# rasp_sheild_i2c.net
KiCad netlist of a schematic drawn in Altium Designer
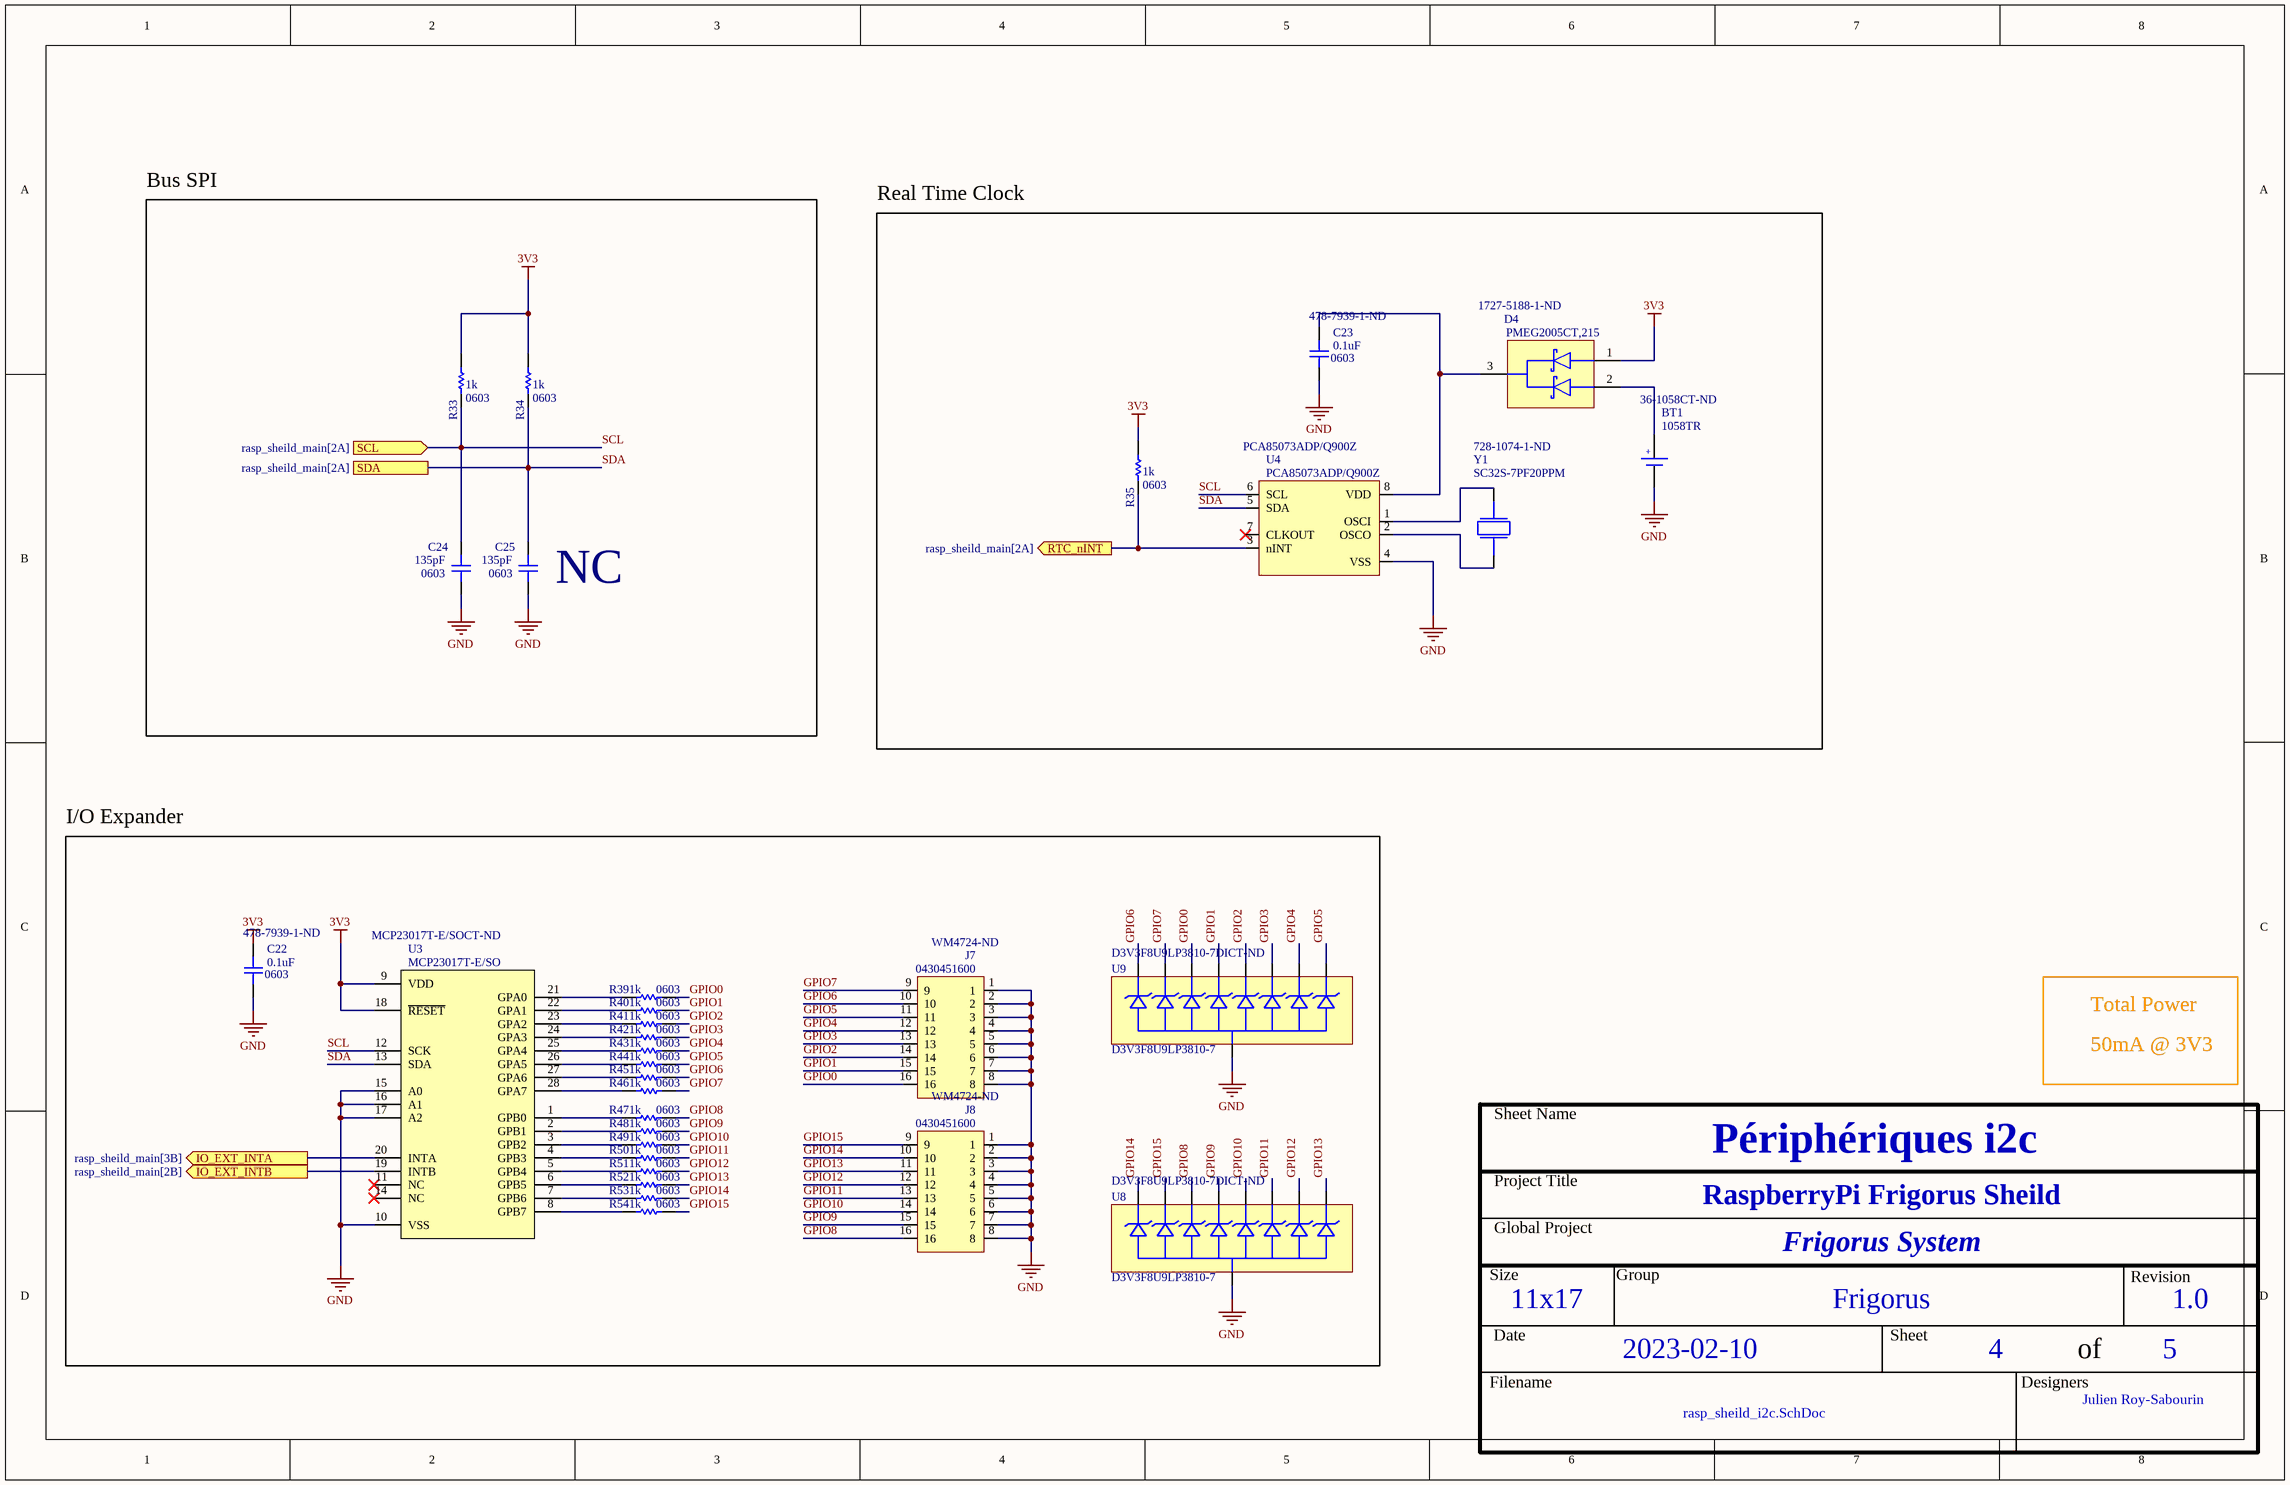
[diagram p0: rasp_sheild_i2c.SchDoc]

(export (version "E")
  (design (tool "Eeschema 10.0.6"))
  (components
    (comp (ref "BT1")
      (value "1058TR")
      (footprint "1058TR")
      (description "Battery Holder (Open) Coin, 20.0mm 1 Cell SMD (SMT) Tab")
      (fields (field (name "SUPPLIER PART NUMBER 1") "36-1058CT-ND"))
      (libsource (lib "royj1311") (part "1058TR"))
    )
    (comp (ref "C22")
      (value "0.1uF")
      (footprint "CAP_0603")
      (description "XXX - Description - Package")
      (fields
        (field (name "PACKAGE") "0603")
        (field (name "SUPPLIER PART NUMBER 1") "478-7939-1-ND")
        (field (name "Comment") "Part Number")
      )
      (libsource (lib "royj1311") (part "CAP_0603"))
    )
    (comp (ref "C23")
      (value "0.1uF")
      (footprint "CAP_0603")
      (description "XXX - Description - Package")
      (fields
        (field (name "PACKAGE") "0603")
        (field (name "SUPPLIER PART NUMBER 1") "478-7939-1-ND")
        (field (name "Comment") "Part Number")
      )
      (libsource (lib "royj1311") (part "CAP_0603"))
    )
    (comp (ref "C24")
      (value "135pF")
      (footprint "CAP_0603")
      (description "XXX - Description - Package")
      (fields (field (name "PACKAGE") "0603") (field (name "Comment") "Part Number"))
      (libsource (lib "royj1311") (part "CAP_0603"))
    )
    (comp (ref "C25")
      (value "135pF")
      (footprint "CAP_0603")
      (description "XXX - Description - Package")
      (fields (field (name "PACKAGE") "0603") (field (name "Comment") "Part Number"))
      (libsource (lib "royj1311") (part "CAP_0603"))
    )
    (comp (ref "D4")
      (value "PMEG2005CT,215")
      (footprint "SOT-23-3")
      (description "Diode Array 1 Pair Common Cathode 20 V 500mA Surface Mount TO-236-3, SC-59, SOT-23-3")
      (fields (field (name "SUPPLIER PART NUMBER 1") "1727-5188-1-ND"))
      (libsource (lib "royj1311") (part "PMEG2005CT,215"))
    )
    (comp (ref "J7")
      (value "0430451600")
      (footprint "0430451600")
      (description "Connector Header Through Hole, Right Angle 16 position 0.118\" (3.00mm)")
      (fields (field (name "SUPPLIER PART NUMBER 1") "WM4724-ND"))
      (libsource (lib "royj1311") (part "0430451600"))
    )
    (comp (ref "J8")
      (value "0430451600")
      (footprint "0430451600")
      (description "Connector Header Through Hole, Right Angle 16 position 0.118\" (3.00mm)")
      (fields (field (name "SUPPLIER PART NUMBER 1") "WM4724-ND"))
      (libsource (lib "royj1311") (part "0430451600"))
    )
    (comp (ref "R33")
      (value "1k")
      (footprint "RES_0603")
      (description "XXX - Description - Package")
      (fields (field (name "PACKAGE") "0603") (field (name "Comment") "Part Number"))
      (libsource (lib "royj1311") (part "RES_0603"))
    )
    (comp (ref "R34")
      (value "1k")
      (footprint "RES_0603")
      (description "XXX - Description - Package")
      (fields (field (name "PACKAGE") "0603") (field (name "Comment") "Part Number"))
      (libsource (lib "royj1311") (part "RES_0603"))
    )
    (comp (ref "R35")
      (value "1k")
      (footprint "RES_0603")
      (description "XXX - Description - Package")
      (fields (field (name "PACKAGE") "0603") (field (name "Comment") "Part Number"))
      (libsource (lib "royj1311") (part "RES_0603"))
    )
    (comp (ref "R39")
      (value "1k")
      (footprint "RES_0603")
      (description "XXX - Description - Package")
      (fields (field (name "PACKAGE") "0603") (field (name "Comment") "Part Number"))
      (libsource (lib "royj1311") (part "RES_0603"))
    )
    (comp (ref "R40")
      (value "1k")
      (footprint "RES_0603")
      (description "XXX - Description - Package")
      (fields (field (name "PACKAGE") "0603") (field (name "Comment") "Part Number"))
      (libsource (lib "royj1311") (part "RES_0603"))
    )
    (comp (ref "R41")
      (value "1k")
      (footprint "RES_0603")
      (description "XXX - Description - Package")
      (fields (field (name "PACKAGE") "0603") (field (name "Comment") "Part Number"))
      (libsource (lib "royj1311") (part "RES_0603"))
    )
    (comp (ref "R42")
      (value "1k")
      (footprint "RES_0603")
      (description "XXX - Description - Package")
      (fields (field (name "PACKAGE") "0603") (field (name "Comment") "Part Number"))
      (libsource (lib "royj1311") (part "RES_0603"))
    )
    (comp (ref "R43")
      (value "1k")
      (footprint "RES_0603")
      (description "XXX - Description - Package")
      (fields (field (name "PACKAGE") "0603") (field (name "Comment") "Part Number"))
      (libsource (lib "royj1311") (part "RES_0603"))
    )
    (comp (ref "R44")
      (value "1k")
      (footprint "RES_0603")
      (description "XXX - Description - Package")
      (fields (field (name "PACKAGE") "0603") (field (name "Comment") "Part Number"))
      (libsource (lib "royj1311") (part "RES_0603"))
    )
    (comp (ref "R45")
      (value "1k")
      (footprint "RES_0603")
      (description "XXX - Description - Package")
      (fields (field (name "PACKAGE") "0603") (field (name "Comment") "Part Number"))
      (libsource (lib "royj1311") (part "RES_0603"))
    )
    (comp (ref "R46")
      (value "1k")
      (footprint "RES_0603")
      (description "XXX - Description - Package")
      (fields (field (name "PACKAGE") "0603") (field (name "Comment") "Part Number"))
      (libsource (lib "royj1311") (part "RES_0603"))
    )
    (comp (ref "R47")
      (value "1k")
      (footprint "RES_0603")
      (description "XXX - Description - Package")
      (fields (field (name "PACKAGE") "0603") (field (name "Comment") "Part Number"))
      (libsource (lib "royj1311") (part "RES_0603"))
    )
    (comp (ref "R48")
      (value "1k")
      (footprint "RES_0603")
      (description "XXX - Description - Package")
      (fields (field (name "PACKAGE") "0603") (field (name "Comment") "Part Number"))
      (libsource (lib "royj1311") (part "RES_0603"))
    )
    (comp (ref "R49")
      (value "1k")
      (footprint "RES_0603")
      (description "XXX - Description - Package")
      (fields (field (name "PACKAGE") "0603") (field (name "Comment") "Part Number"))
      (libsource (lib "royj1311") (part "RES_0603"))
    )
    (comp (ref "R50")
      (value "1k")
      (footprint "RES_0603")
      (description "XXX - Description - Package")
      (fields (field (name "PACKAGE") "0603") (field (name "Comment") "Part Number"))
      (libsource (lib "royj1311") (part "RES_0603"))
    )
    (comp (ref "R51")
      (value "1k")
      (footprint "RES_0603")
      (description "XXX - Description - Package")
      (fields (field (name "PACKAGE") "0603") (field (name "Comment") "Part Number"))
      (libsource (lib "royj1311") (part "RES_0603"))
    )
    (comp (ref "R52")
      (value "1k")
      (footprint "RES_0603")
      (description "XXX - Description - Package")
      (fields (field (name "PACKAGE") "0603") (field (name "Comment") "Part Number"))
      (libsource (lib "royj1311") (part "RES_0603"))
    )
    (comp (ref "R53")
      (value "1k")
      (footprint "RES_0603")
      (description "XXX - Description - Package")
      (fields (field (name "PACKAGE") "0603") (field (name "Comment") "Part Number"))
      (libsource (lib "royj1311") (part "RES_0603"))
    )
    (comp (ref "R54")
      (value "1k")
      (footprint "RES_0603")
      (description "XXX - Description - Package")
      (fields (field (name "PACKAGE") "0603") (field (name "Comment") "Part Number"))
      (libsource (lib "royj1311") (part "RES_0603"))
    )
    (comp (ref "U3")
      (value "MCP23017T-E/SO")
      (footprint "28-SOIC")
      (description "I/O Expander 16 I²C 1.7 MHz 28-SOIC")
      (fields (field (name "SUPPLIER PART NUMBER 1") "MCP23017T-E/SOCT-ND"))
      (libsource (lib "royj1311") (part "MCP23017T-E/SO"))
    )
    (comp (ref "U4")
      (value "PCA85073ADP/Q900Z")
      (footprint "8-MSOP")
      (description "Real Time Clock (RTC) IC Clock/Calendar I²C 8-TSSOP, 8-MSOP (0.118\", 3.00mm Width)")
      (fields (field (name "SUPPLIER PART NUMBER 1") "PCA85073ADP/Q900Z"))
      (libsource (lib "royj1311") (part "PCA85073ADP/Q900Z"))
    )
    (comp (ref "U8")
      (value "D3V3F8U9LP3810-7")
      (footprint "D3V3F8U9LP3810-7")
      (description "5V (Typ) Clamp 5A (8/20µs) Ipp Tvs Diode Surface Mount U-DFN3810-9 (Type B)")
      (fields (field (name "SUPPLIER PART NUMBER 1") "D3V3F8U9LP3810-7DICT-ND"))
      (libsource (lib "royj1311") (part "D3V3F8U9LP3810-7"))
    )
    (comp (ref "U9")
      (value "D3V3F8U9LP3810-7")
      (footprint "D3V3F8U9LP3810-7")
      (description "5V (Typ) Clamp 5A (8/20µs) Ipp Tvs Diode Surface Mount U-DFN3810-9 (Type B)")
      (fields (field (name "SUPPLIER PART NUMBER 1") "D3V3F8U9LP3810-7DICT-ND"))
      (libsource (lib "royj1311") (part "D3V3F8U9LP3810-7"))
    )
    (comp (ref "Y1")
      (value "SC32S-7PF20PPM")
      (footprint "SC32S-7PF20PPM")
      (description "32.768 kHz ±20ppm Crystal 7pF 70 kOhms 2-SMD, No Lead")
      (fields (field (name "SUPPLIER PART NUMBER 1") "728-1074-1-ND"))
      (libsource (lib "royj1311") (part "SC32S-7PF20PPM"))
    )
  )
  (nets
    (net (code "1") (name "/GPIO0") (class "Default")
      (node (ref "J7") (pin "16") (pinfunction "16_16") (pintype "passive"))
      (node (ref "R39") (pin "1") (pinfunction "1_1") (pintype "passive"))
      (node (ref "U9") (pin "4") (pinfunction "4_4") (pintype "passive"))
    )
    (net (code "2") (name "/GPIO1") (class "Default")
      (node (ref "J7") (pin "15") (pinfunction "15_15") (pintype "passive"))
      (node (ref "R40") (pin "1") (pinfunction "1_1") (pintype "passive"))
      (node (ref "U9") (pin "5") (pinfunction "5_5") (pintype "passive"))
    )
    (net (code "3") (name "/GPIO2") (class "Default")
      (node (ref "J7") (pin "14") (pinfunction "14_14") (pintype "passive"))
      (node (ref "R41") (pin "1") (pinfunction "1_1") (pintype "passive"))
      (node (ref "U9") (pin "6") (pinfunction "6_6") (pintype "passive"))
    )
    (net (code "4") (name "/GPIO3") (class "Default")
      (node (ref "J7") (pin "13") (pinfunction "13_13") (pintype "passive"))
      (node (ref "R42") (pin "1") (pinfunction "1_1") (pintype "passive"))
      (node (ref "U9") (pin "7") (pinfunction "7_7") (pintype "passive"))
    )
    (net (code "5") (name "/GPIO4") (class "Default")
      (node (ref "J7") (pin "12") (pinfunction "12_12") (pintype "passive"))
      (node (ref "R43") (pin "1") (pinfunction "1_1") (pintype "passive"))
      (node (ref "U9") (pin "8") (pinfunction "8_8") (pintype "passive"))
    )
    (net (code "6") (name "/GPIO5") (class "Default")
      (node (ref "J7") (pin "11") (pinfunction "11_11") (pintype "passive"))
      (node (ref "R44") (pin "1") (pinfunction "1_1") (pintype "passive"))
      (node (ref "U9") (pin "9") (pinfunction "9_9") (pintype "passive"))
    )
    (net (code "7") (name "/GPIO6") (class "Default")
      (node (ref "J7") (pin "10") (pinfunction "10_10") (pintype "passive"))
      (node (ref "R45") (pin "1") (pinfunction "1_1") (pintype "passive"))
      (node (ref "U9") (pin "1") (pinfunction "1_1") (pintype "passive"))
    )
    (net (code "8") (name "/GPIO7") (class "Default")
      (node (ref "J7") (pin "9") (pinfunction "9_9") (pintype "passive"))
      (node (ref "R46") (pin "1") (pinfunction "1_1") (pintype "passive"))
      (node (ref "U9") (pin "2") (pinfunction "2_2") (pintype "passive"))
    )
    (net (code "9") (name "/GPIO8") (class "Default")
      (node (ref "J8") (pin "16") (pinfunction "16_16") (pintype "passive"))
      (node (ref "R47") (pin "1") (pinfunction "1_1") (pintype "passive"))
      (node (ref "U8") (pin "4") (pinfunction "4_4") (pintype "passive"))
    )
    (net (code "10") (name "/GPIO9") (class "Default")
      (node (ref "J8") (pin "15") (pinfunction "15_15") (pintype "passive"))
      (node (ref "R48") (pin "1") (pinfunction "1_1") (pintype "passive"))
      (node (ref "U8") (pin "5") (pinfunction "5_5") (pintype "passive"))
    )
    (net (code "11") (name "/GPIO10") (class "Default")
      (node (ref "J8") (pin "14") (pinfunction "14_14") (pintype "passive"))
      (node (ref "R49") (pin "1") (pinfunction "1_1") (pintype "passive"))
      (node (ref "U8") (pin "6") (pinfunction "6_6") (pintype "passive"))
    )
    (net (code "12") (name "/GPIO11") (class "Default")
      (node (ref "J8") (pin "13") (pinfunction "13_13") (pintype "passive"))
      (node (ref "R50") (pin "1") (pinfunction "1_1") (pintype "passive"))
      (node (ref "U8") (pin "7") (pinfunction "7_7") (pintype "passive"))
    )
    (net (code "13") (name "/GPIO12") (class "Default")
      (node (ref "J8") (pin "12") (pinfunction "12_12") (pintype "passive"))
      (node (ref "R51") (pin "1") (pinfunction "1_1") (pintype "passive"))
      (node (ref "U8") (pin "8") (pinfunction "8_8") (pintype "passive"))
    )
    (net (code "14") (name "/GPIO13") (class "Default")
      (node (ref "J8") (pin "11") (pinfunction "11_11") (pintype "passive"))
      (node (ref "R52") (pin "1") (pinfunction "1_1") (pintype "passive"))
      (node (ref "U8") (pin "9") (pinfunction "9_9") (pintype "passive"))
    )
    (net (code "15") (name "/GPIO14") (class "Default")
      (node (ref "J8") (pin "10") (pinfunction "10_10") (pintype "passive"))
      (node (ref "R53") (pin "1") (pinfunction "1_1") (pintype "passive"))
      (node (ref "U8") (pin "1") (pinfunction "1_1") (pintype "passive"))
    )
    (net (code "16") (name "/GPIO15") (class "Default")
      (node (ref "J8") (pin "9") (pinfunction "9_9") (pintype "passive"))
      (node (ref "R54") (pin "1") (pinfunction "1_1") (pintype "passive"))
      (node (ref "U8") (pin "2") (pinfunction "2_2") (pintype "passive"))
    )
    (net (code "17") (name "/IO_EXT_INTA") (class "Default")
      (node (ref "U3") (pin "20") (pinfunction "INTA_20") (pintype "passive"))
    )
    (net (code "18") (name "/IO_EXT_INTB") (class "Default")
      (node (ref "U3") (pin "19") (pinfunction "INTB_19") (pintype "passive"))
    )
    (net (code "19") (name "/RTC_nINT") (class "Default")
      (node (ref "R35") (pin "2") (pinfunction "2_2") (pintype "passive"))
      (node (ref "U4") (pin "3") (pinfunction "nINT_3") (pintype "passive"))
    )
    (net (code "20") (name "/SCL") (class "Default")
      (node (ref "C24") (pin "2") (pinfunction "2_2") (pintype "passive"))
      (node (ref "R33") (pin "2") (pinfunction "2_2") (pintype "passive"))
      (node (ref "U3") (pin "12") (pinfunction "SCK_12") (pintype "passive"))
      (node (ref "U4") (pin "6") (pinfunction "SCL_6") (pintype "passive"))
    )
    (net (code "21") (name "/SDA") (class "Default")
      (node (ref "C25") (pin "2") (pinfunction "2_2") (pintype "passive"))
      (node (ref "R34") (pin "2") (pinfunction "2_2") (pintype "passive"))
      (node (ref "U3") (pin "13") (pinfunction "SDA_13") (pintype "passive"))
      (node (ref "U4") (pin "5") (pinfunction "SDA_5") (pintype "passive"))
    )
    (net (code "22") (name "3V3") (class "Default")
      (node (ref "C22") (pin "2") (pinfunction "2_2") (pintype "passive"))
      (node (ref "D4") (pin "1") (pinfunction "1_1") (pintype "passive"))
      (node (ref "R33") (pin "1") (pinfunction "1_1") (pintype "passive"))
      (node (ref "R34") (pin "1") (pinfunction "1_1") (pintype "passive"))
      (node (ref "R35") (pin "1") (pinfunction "1_1") (pintype "passive"))
      (node (ref "U3") (pin "18") (pinfunction "~{RESET}_18") (pintype "passive"))
      (node (ref "U3") (pin "9") (pinfunction "VDD_9") (pintype "passive"))
    )
    (net (code "23") (name "GND") (class "Default")
      (node (ref "BT1") (pin "2") (pinfunction "-_2") (pintype "passive"))
      (node (ref "C22") (pin "1") (pinfunction "1_1") (pintype "passive"))
      (node (ref "C23") (pin "1") (pinfunction "1_1") (pintype "passive"))
      (node (ref "C24") (pin "1") (pinfunction "1_1") (pintype "passive"))
      (node (ref "C25") (pin "1") (pinfunction "1_1") (pintype "passive"))
      (node (ref "J7") (pin "1") (pinfunction "1_1") (pintype "passive"))
      (node (ref "J7") (pin "2") (pinfunction "2_2") (pintype "passive"))
      (node (ref "J7") (pin "3") (pinfunction "3_3") (pintype "passive"))
      (node (ref "J7") (pin "4") (pinfunction "4_4") (pintype "passive"))
      (node (ref "J7") (pin "5") (pinfunction "5_5") (pintype "passive"))
      (node (ref "J7") (pin "6") (pinfunction "6_6") (pintype "passive"))
      (node (ref "J7") (pin "7") (pinfunction "7_7") (pintype "passive"))
      (node (ref "J7") (pin "8") (pinfunction "8_8") (pintype "passive"))
      (node (ref "J8") (pin "1") (pinfunction "1_1") (pintype "passive"))
      (node (ref "J8") (pin "2") (pinfunction "2_2") (pintype "passive"))
      (node (ref "J8") (pin "3") (pinfunction "3_3") (pintype "passive"))
      (node (ref "J8") (pin "4") (pinfunction "4_4") (pintype "passive"))
      (node (ref "J8") (pin "5") (pinfunction "5_5") (pintype "passive"))
      (node (ref "J8") (pin "6") (pinfunction "6_6") (pintype "passive"))
      (node (ref "J8") (pin "7") (pinfunction "7_7") (pintype "passive"))
      (node (ref "J8") (pin "8") (pinfunction "8_8") (pintype "passive"))
      (node (ref "U3") (pin "10") (pinfunction "VSS_10") (pintype "passive"))
      (node (ref "U3") (pin "15") (pinfunction "A0_15") (pintype "passive"))
      (node (ref "U3") (pin "16") (pinfunction "A1_16") (pintype "passive"))
      (node (ref "U3") (pin "17") (pinfunction "A2_17") (pintype "passive"))
      (node (ref "U4") (pin "4") (pinfunction "VSS_4") (pintype "passive"))
      (node (ref "U8") (pin "3") (pinfunction "3_3") (pintype "passive"))
      (node (ref "U9") (pin "3") (pinfunction "3_3") (pintype "passive"))
    )
    (net (code "24") (name "Net-(BT1-+)") (class "Default")
      (node (ref "BT1") (pin "1") (pinfunction "+_1") (pintype "passive"))
      (node (ref "D4") (pin "2") (pinfunction "2_2") (pintype "passive"))
    )
    (net (code "25") (name "Net-(U3-GPA0)") (class "Default")
      (node (ref "R39") (pin "2") (pinfunction "2_2") (pintype "passive"))
      (node (ref "U3") (pin "21") (pinfunction "GPA0_21") (pintype "passive"))
    )
    (net (code "26") (name "Net-(U3-GPA1)") (class "Default")
      (node (ref "R40") (pin "2") (pinfunction "2_2") (pintype "passive"))
      (node (ref "U3") (pin "22") (pinfunction "GPA1_22") (pintype "passive"))
    )
    (net (code "27") (name "Net-(U3-GPA2)") (class "Default")
      (node (ref "R41") (pin "2") (pinfunction "2_2") (pintype "passive"))
      (node (ref "U3") (pin "23") (pinfunction "GPA2_23") (pintype "passive"))
    )
    (net (code "28") (name "Net-(U3-GPA3)") (class "Default")
      (node (ref "R42") (pin "2") (pinfunction "2_2") (pintype "passive"))
      (node (ref "U3") (pin "24") (pinfunction "GPA3_24") (pintype "passive"))
    )
    (net (code "29") (name "Net-(U3-GPA4)") (class "Default")
      (node (ref "R43") (pin "2") (pinfunction "2_2") (pintype "passive"))
      (node (ref "U3") (pin "25") (pinfunction "GPA4_25") (pintype "passive"))
    )
    (net (code "30") (name "Net-(U3-GPA5)") (class "Default")
      (node (ref "R44") (pin "2") (pinfunction "2_2") (pintype "passive"))
      (node (ref "U3") (pin "26") (pinfunction "GPA5_26") (pintype "passive"))
    )
    (net (code "31") (name "Net-(U3-GPA6)") (class "Default")
      (node (ref "R45") (pin "2") (pinfunction "2_2") (pintype "passive"))
      (node (ref "U3") (pin "27") (pinfunction "GPA6_27") (pintype "passive"))
    )
    (net (code "32") (name "Net-(U3-GPA7)") (class "Default")
      (node (ref "R46") (pin "2") (pinfunction "2_2") (pintype "passive"))
      (node (ref "U3") (pin "28") (pinfunction "GPA7_28") (pintype "passive"))
    )
    (net (code "33") (name "Net-(U3-GPB0)") (class "Default")
      (node (ref "R47") (pin "2") (pinfunction "2_2") (pintype "passive"))
      (node (ref "U3") (pin "1") (pinfunction "GPB0_1") (pintype "passive"))
    )
    (net (code "34") (name "Net-(U3-GPB1)") (class "Default")
      (node (ref "R48") (pin "2") (pinfunction "2_2") (pintype "passive"))
      (node (ref "U3") (pin "2") (pinfunction "GPB1_2") (pintype "passive"))
    )
    (net (code "35") (name "Net-(U3-GPB2)") (class "Default")
      (node (ref "R49") (pin "2") (pinfunction "2_2") (pintype "passive"))
      (node (ref "U3") (pin "3") (pinfunction "GPB2_3") (pintype "passive"))
    )
    (net (code "36") (name "Net-(U3-GPB3)") (class "Default")
      (node (ref "R50") (pin "2") (pinfunction "2_2") (pintype "passive"))
      (node (ref "U3") (pin "4") (pinfunction "GPB3_4") (pintype "passive"))
    )
    (net (code "37") (name "Net-(U3-GPB4)") (class "Default")
      (node (ref "R51") (pin "2") (pinfunction "2_2") (pintype "passive"))
      (node (ref "U3") (pin "5") (pinfunction "GPB4_5") (pintype "passive"))
    )
    (net (code "38") (name "Net-(U3-GPB5)") (class "Default")
      (node (ref "R52") (pin "2") (pinfunction "2_2") (pintype "passive"))
      (node (ref "U3") (pin "6") (pinfunction "GPB5_6") (pintype "passive"))
    )
    (net (code "39") (name "Net-(U3-GPB6)") (class "Default")
      (node (ref "R53") (pin "2") (pinfunction "2_2") (pintype "passive"))
      (node (ref "U3") (pin "7") (pinfunction "GPB6_7") (pintype "passive"))
    )
    (net (code "40") (name "Net-(U3-GPB7)") (class "Default")
      (node (ref "R54") (pin "2") (pinfunction "2_2") (pintype "passive"))
      (node (ref "U3") (pin "8") (pinfunction "GPB7_8") (pintype "passive"))
    )
    (net (code "41") (name "Net-(U4-OSCI)") (class "Default")
      (node (ref "U4") (pin "1") (pinfunction "OSCI_1") (pintype "passive"))
      (node (ref "Y1") (pin "2") (pinfunction "2_2") (pintype "passive"))
    )
    (net (code "42") (name "Net-(U4-OSCO)") (class "Default")
      (node (ref "U4") (pin "2") (pinfunction "OSCO_2") (pintype "passive"))
      (node (ref "Y1") (pin "1") (pinfunction "1_1") (pintype "passive"))
    )
    (net (code "43") (name "Net-(U4-VDD)") (class "Default")
      (node (ref "C23") (pin "2") (pinfunction "2_2") (pintype "passive"))
      (node (ref "D4") (pin "3") (pinfunction "3_3") (pintype "passive"))
      (node (ref "U4") (pin "8") (pinfunction "VDD_8") (pintype "passive"))
    )
    (net (code "44") (name "unconnected-(U3-NC-Pad11)") (class "Default")
      (node (ref "U3") (pin "11") (pinfunction "NC_11") (pintype "passive+no_connect"))
    )
    (net (code "45") (name "unconnected-(U3-NC-Pad14)") (class "Default")
      (node (ref "U3") (pin "14") (pinfunction "NC_14") (pintype "passive+no_connect"))
    )
    (net (code "46") (name "unconnected-(U4-CLKOUT-Pad7)") (class "Default")
      (node (ref "U4") (pin "7") (pinfunction "CLKOUT_7") (pintype "passive+no_connect"))
    )
  )
)
